# isg_AL11b_equip_chip_board_passive.net
KiCad netlist of a schematic drawn in Altium Designer
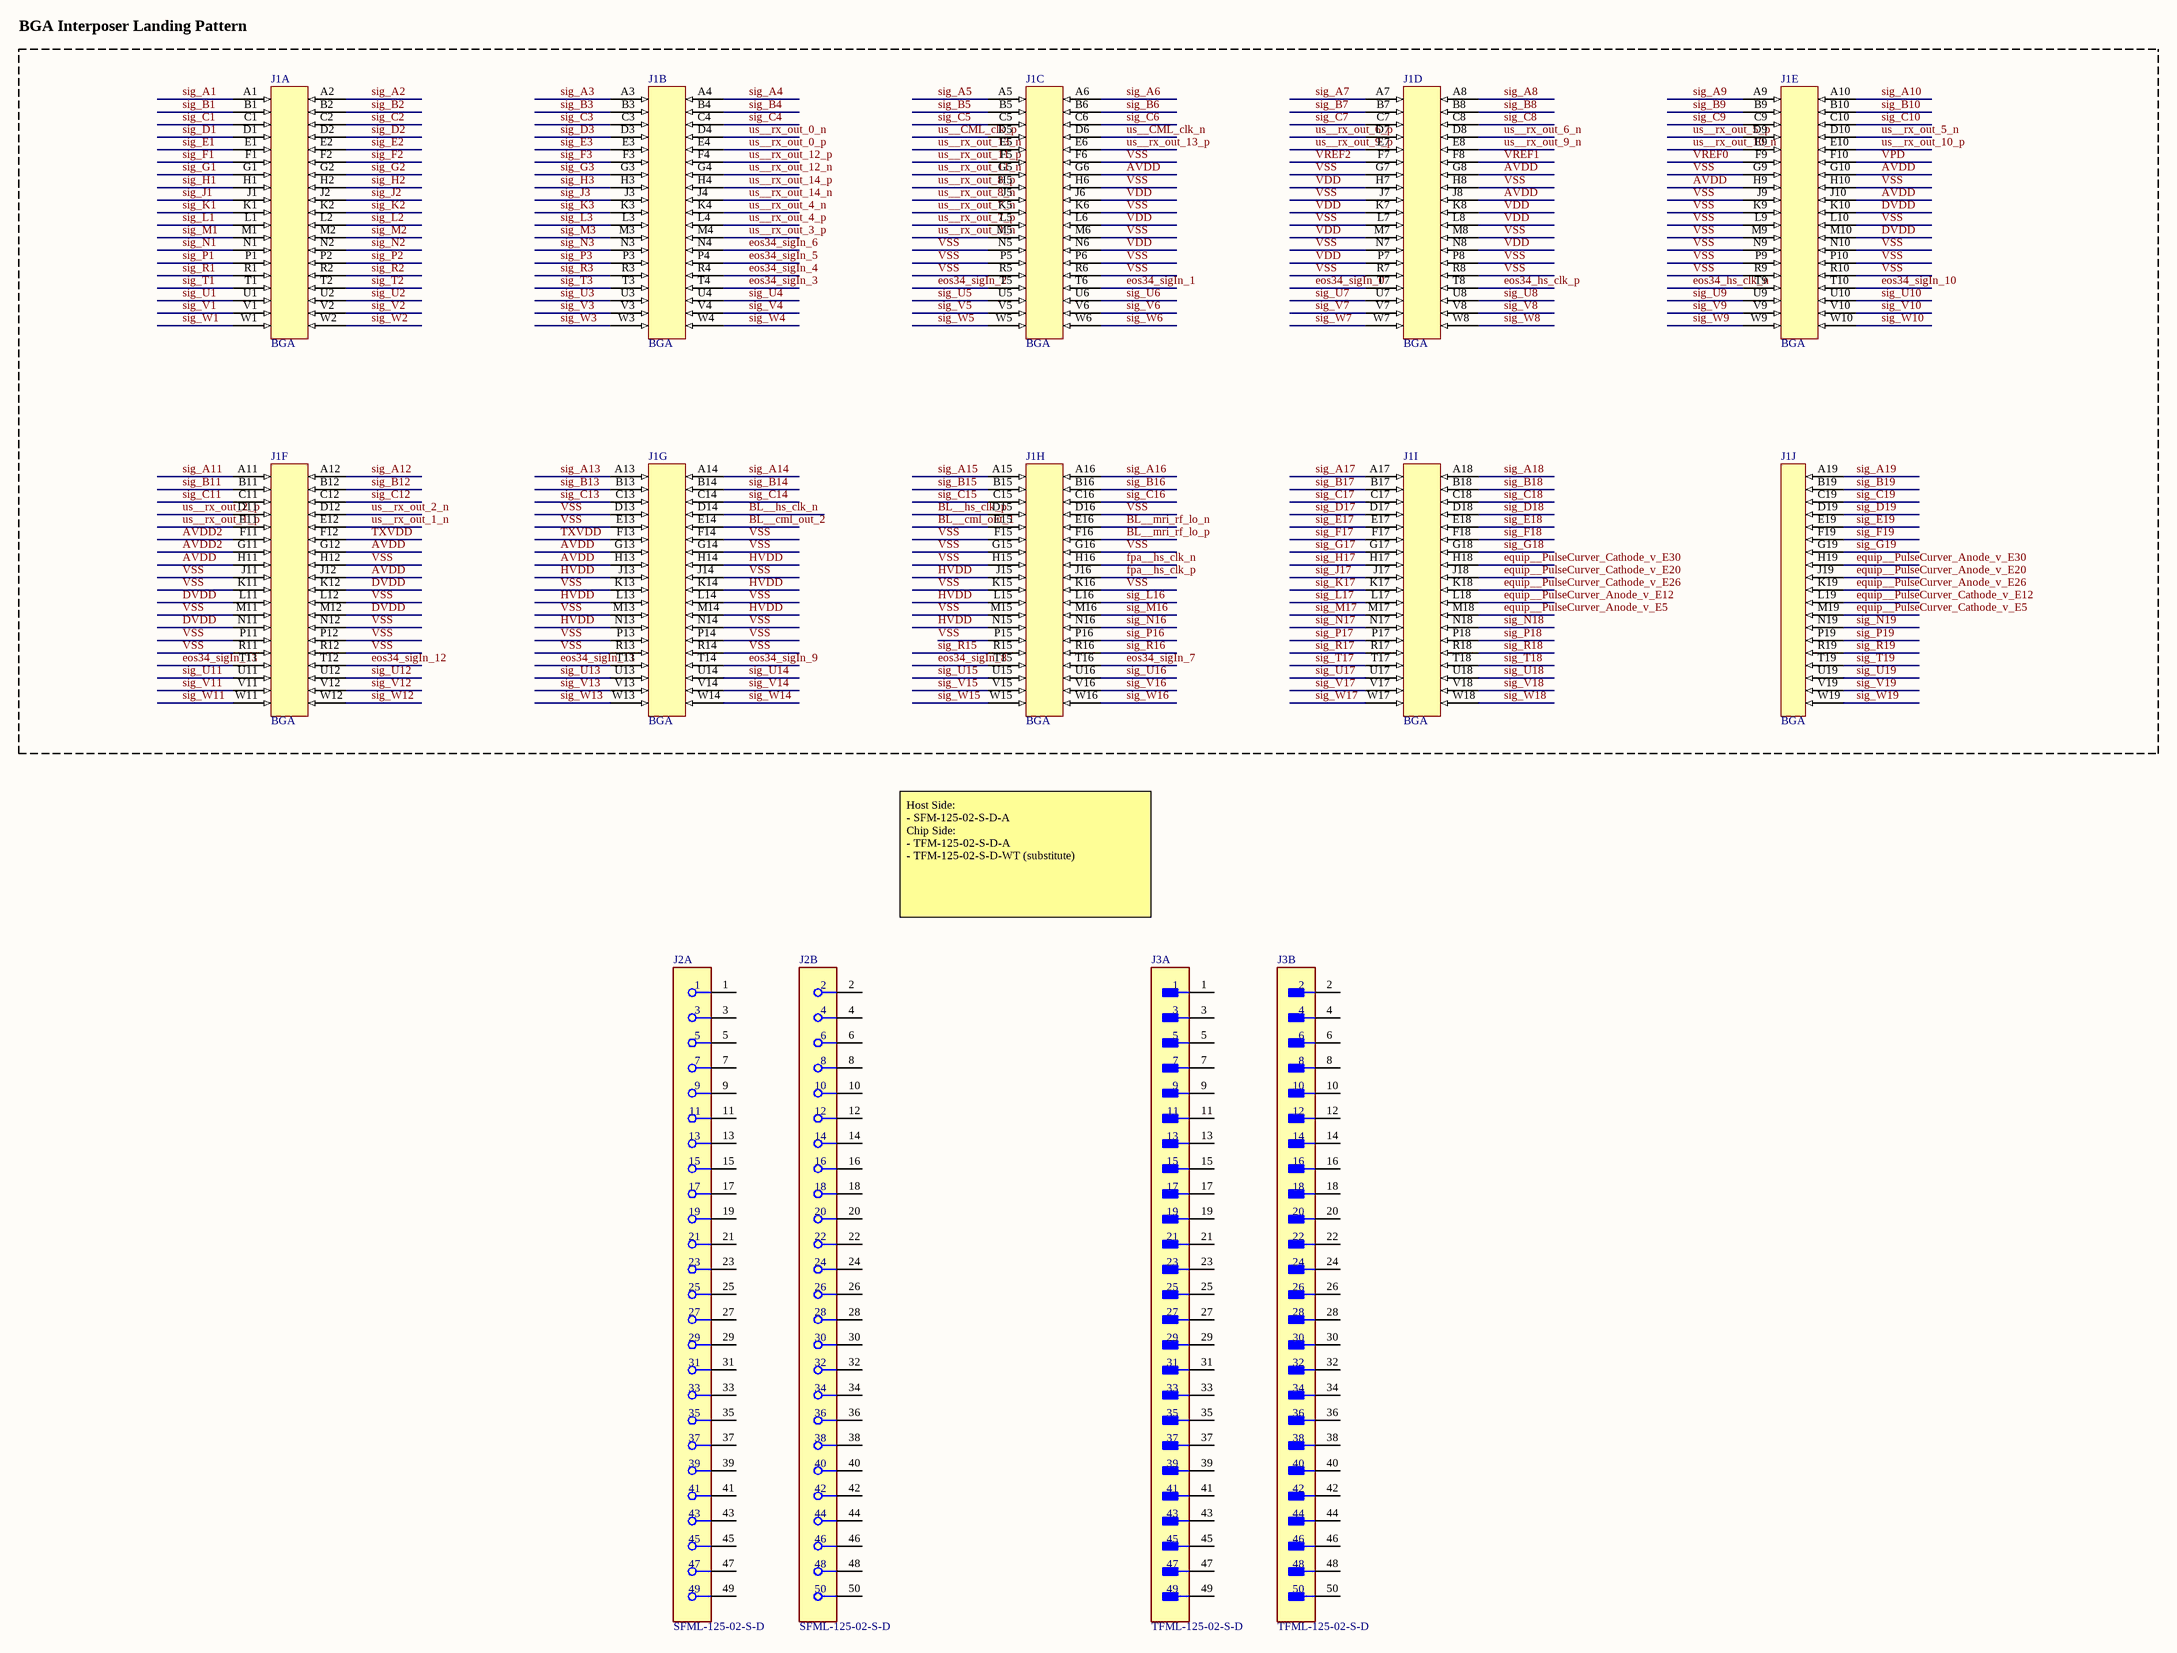
[diagram p0: isg_AL11b_equip_chip_board_passive.SchDoc]

(export (version "E")
  (design (tool "Eeschema 10.0.6"))
  (components
    (comp (ref "J1")
      (value "BGA")
      (footprint "BGA361x19_CHIP_BOARD_TOP")
      (libsource (lib "AL11b") (part "BGA"))
    )
    (comp (ref "J2")
      (value "SFML-125-02-S-D")
      (footprint "FP-SFML-125-02-S-D-MFG")
      (description "CONN RCPT 50POS 0.05 GOLD SMD")
      (libsource (lib "Altium Content Vault") (part "81018408ad8334d3fec81fb021a27ac"))
    )
    (comp (ref "J3")
      (value "TFML-125-02-S-D")
      (footprint "FP-TFML-125-02-S-D-MFG")
      (description "CONN HEADER SMD 50POS 1.27MM")
      (libsource (lib "Altium Content Vault") (part "0c4f4a43de66d56b98fa02f2c160411"))
    )
  )
  (nets
    (net (code "1") (name "/AVDD") (class "Default")
      (node (ref "J1") (pin "G10") (pintype "input"))
      (node (ref "J1") (pin "G12") (pintype "input"))
      (node (ref "J1") (pin "G13") (pintype "input"))
      (node (ref "J1") (pin "G6") (pintype "input"))
      (node (ref "J1") (pin "G8") (pintype "input"))
      (node (ref "J1") (pin "H11") (pintype "input"))
      (node (ref "J1") (pin "H13") (pintype "input"))
      (node (ref "J1") (pin "H9") (pintype "input"))
      (node (ref "J1") (pin "J10") (pintype "input"))
      (node (ref "J1") (pin "J12") (pintype "input"))
      (node (ref "J1") (pin "J8") (pintype "input"))
    )
    (net (code "2") (name "/AVDD2") (class "Default")
      (node (ref "J1") (pin "F11") (pintype "input"))
      (node (ref "J1") (pin "G11") (pintype "input"))
    )
    (net (code "3") (name "/BL__cml_out_1") (class "Default") (node (ref "J1") (pin "E15") (pintype "input")))
    (net (code "4") (name "/BL__cml_out_2") (class "Default") (node (ref "J1") (pin "E14") (pintype "input")))
    (net (code "5") (name "/BL__hs_clk_n") (class "Default") (node (ref "J1") (pin "D14") (pintype "input")))
    (net (code "6") (name "/BL__hs_clk_p") (class "Default") (node (ref "J1") (pin "D15") (pintype "input")))
    (net (code "7") (name "/BL__mri_rf_lo_n") (class "Default")
      (node (ref "J1") (pin "E16") (pintype "input"))
    )
    (net (code "8") (name "/BL__mri_rf_lo_p") (class "Default")
      (node (ref "J1") (pin "F16") (pintype "input"))
    )
    (net (code "9") (name "/DVDD") (class "Default")
      (node (ref "J1") (pin "K10") (pintype "input"))
      (node (ref "J1") (pin "K12") (pintype "input"))
      (node (ref "J1") (pin "L11") (pintype "input"))
      (node (ref "J1") (pin "M10") (pintype "input"))
      (node (ref "J1") (pin "M12") (pintype "input"))
      (node (ref "J1") (pin "N11") (pintype "input"))
    )
    (net (code "10") (name "/HVDD") (class "Default")
      (node (ref "J1") (pin "H14") (pintype "input"))
      (node (ref "J1") (pin "J13") (pintype "input"))
      (node (ref "J1") (pin "J15") (pintype "input"))
      (node (ref "J1") (pin "K14") (pintype "input"))
      (node (ref "J1") (pin "L13") (pintype "input"))
      (node (ref "J1") (pin "L15") (pintype "input"))
      (node (ref "J1") (pin "M14") (pintype "input"))
      (node (ref "J1") (pin "N13") (pintype "input"))
      (node (ref "J1") (pin "N15") (pintype "input"))
    )
    (net (code "11") (name "/TXVDD") (class "Default")
      (node (ref "J1") (pin "F12") (pintype "input"))
      (node (ref "J1") (pin "F13") (pintype "input"))
    )
    (net (code "12") (name "/VDD") (class "Default")
      (node (ref "J1") (pin "H7") (pintype "input"))
      (node (ref "J1") (pin "J6") (pintype "input"))
      (node (ref "J1") (pin "K7") (pintype "input"))
      (node (ref "J1") (pin "K8") (pintype "input"))
      (node (ref "J1") (pin "L6") (pintype "input"))
      (node (ref "J1") (pin "L8") (pintype "input"))
      (node (ref "J1") (pin "M7") (pintype "input"))
      (node (ref "J1") (pin "N6") (pintype "input"))
      (node (ref "J1") (pin "N8") (pintype "input"))
      (node (ref "J1") (pin "P7") (pintype "input"))
    )
    (net (code "13") (name "/VPD") (class "Default") (node (ref "J1") (pin "F10") (pintype "input")))
    (net (code "14") (name "/VREF0") (class "Default") (node (ref "J1") (pin "F9") (pintype "input")))
    (net (code "15") (name "/VREF1") (class "Default") (node (ref "J1") (pin "F8") (pintype "input")))
    (net (code "16") (name "/VREF2") (class "Default") (node (ref "J1") (pin "F7") (pintype "input")))
    (net (code "17") (name "/VSS") (class "Default")
      (node (ref "J1") (pin "D13") (pintype "input"))
      (node (ref "J1") (pin "D16") (pintype "input"))
      (node (ref "J1") (pin "E13") (pintype "input"))
      (node (ref "J1") (pin "F14") (pintype "input"))
      (node (ref "J1") (pin "F15") (pintype "input"))
      (node (ref "J1") (pin "F6") (pintype "input"))
      (node (ref "J1") (pin "G14") (pintype "input"))
      (node (ref "J1") (pin "G15") (pintype "input"))
      (node (ref "J1") (pin "G16") (pintype "input"))
      (node (ref "J1") (pin "G7") (pintype "input"))
      (node (ref "J1") (pin "G9") (pintype "input"))
      (node (ref "J1") (pin "H10") (pintype "input"))
      (node (ref "J1") (pin "H12") (pintype "input"))
      (node (ref "J1") (pin "H15") (pintype "input"))
      (node (ref "J1") (pin "H6") (pintype "input"))
      (node (ref "J1") (pin "H8") (pintype "input"))
      (node (ref "J1") (pin "J11") (pintype "input"))
      (node (ref "J1") (pin "J14") (pintype "input"))
      (node (ref "J1") (pin "J7") (pintype "input"))
      (node (ref "J1") (pin "J9") (pintype "input"))
      (node (ref "J1") (pin "K11") (pintype "input"))
      (node (ref "J1") (pin "K13") (pintype "input"))
      (node (ref "J1") (pin "K15") (pintype "input"))
      (node (ref "J1") (pin "K16") (pintype "input"))
      (node (ref "J1") (pin "K6") (pintype "input"))
      (node (ref "J1") (pin "K9") (pintype "input"))
      (node (ref "J1") (pin "L10") (pintype "input"))
      (node (ref "J1") (pin "L12") (pintype "input"))
      (node (ref "J1") (pin "L14") (pintype "input"))
      (node (ref "J1") (pin "L7") (pintype "input"))
      (node (ref "J1") (pin "L9") (pintype "input"))
      (node (ref "J1") (pin "M11") (pintype "input"))
      (node (ref "J1") (pin "M13") (pintype "input"))
      (node (ref "J1") (pin "M15") (pintype "input"))
      (node (ref "J1") (pin "M6") (pintype "input"))
      (node (ref "J1") (pin "M8") (pintype "input"))
      (node (ref "J1") (pin "M9") (pintype "input"))
      (node (ref "J1") (pin "N10") (pintype "input"))
      (node (ref "J1") (pin "N12") (pintype "input"))
      (node (ref "J1") (pin "N14") (pintype "input"))
      (node (ref "J1") (pin "N5") (pintype "input"))
      (node (ref "J1") (pin "N7") (pintype "input"))
      (node (ref "J1") (pin "N9") (pintype "input"))
      (node (ref "J1") (pin "P10") (pintype "input"))
      (node (ref "J1") (pin "P11") (pintype "input"))
      (node (ref "J1") (pin "P12") (pintype "input"))
      (node (ref "J1") (pin "P13") (pintype "input"))
      (node (ref "J1") (pin "P14") (pintype "input"))
      (node (ref "J1") (pin "P15") (pintype "input"))
      (node (ref "J1") (pin "P5") (pintype "input"))
      (node (ref "J1") (pin "P6") (pintype "input"))
      (node (ref "J1") (pin "P8") (pintype "input"))
      (node (ref "J1") (pin "P9") (pintype "input"))
      (node (ref "J1") (pin "R10") (pintype "input"))
      (node (ref "J1") (pin "R11") (pintype "input"))
      (node (ref "J1") (pin "R12") (pintype "input"))
      (node (ref "J1") (pin "R13") (pintype "input"))
      (node (ref "J1") (pin "R14") (pintype "input"))
      (node (ref "J1") (pin "R5") (pintype "input"))
      (node (ref "J1") (pin "R6") (pintype "input"))
      (node (ref "J1") (pin "R7") (pintype "input"))
      (node (ref "J1") (pin "R8") (pintype "input"))
      (node (ref "J1") (pin "R9") (pintype "input"))
    )
    (net (code "18") (name "/eos34_hs_clk_n") (class "Default")
      (node (ref "J1") (pin "T9") (pintype "input"))
    )
    (net (code "19") (name "/eos34_hs_clk_p") (class "Default")
      (node (ref "J1") (pin "T8") (pintype "input"))
    )
    (net (code "20") (name "/eos34_sigIn_0") (class "Default") (node (ref "J1") (pin "T7") (pintype "input")))
    (net (code "21") (name "/eos34_sigIn_1") (class "Default") (node (ref "J1") (pin "T6") (pintype "input")))
    (net (code "22") (name "/eos34_sigIn_2") (class "Default") (node (ref "J1") (pin "T5") (pintype "input")))
    (net (code "23") (name "/eos34_sigIn_3") (class "Default") (node (ref "J1") (pin "T4") (pintype "input")))
    (net (code "24") (name "/eos34_sigIn_4") (class "Default") (node (ref "J1") (pin "R4") (pintype "input")))
    (net (code "25") (name "/eos34_sigIn_5") (class "Default") (node (ref "J1") (pin "P4") (pintype "input")))
    (net (code "26") (name "/eos34_sigIn_6") (class "Default") (node (ref "J1") (pin "N4") (pintype "input")))
    (net (code "27") (name "/eos34_sigIn_7") (class "Default")
      (node (ref "J1") (pin "T16") (pintype "input"))
    )
    (net (code "28") (name "/eos34_sigIn_8") (class "Default")
      (node (ref "J1") (pin "T15") (pintype "input"))
    )
    (net (code "29") (name "/eos34_sigIn_9") (class "Default")
      (node (ref "J1") (pin "T14") (pintype "input"))
    )
    (net (code "30") (name "/eos34_sigIn_10") (class "Default")
      (node (ref "J1") (pin "T10") (pintype "input"))
    )
    (net (code "31") (name "/eos34_sigIn_11") (class "Default")
      (node (ref "J1") (pin "T13") (pintype "input"))
    )
    (net (code "32") (name "/eos34_sigIn_12") (class "Default")
      (node (ref "J1") (pin "T12") (pintype "input"))
    )
    (net (code "33") (name "/eos34_sigIn_13") (class "Default")
      (node (ref "J1") (pin "T11") (pintype "input"))
    )
    (net (code "34") (name "/equip__PulseCurver_Anode_v_E5") (class "Default")
      (node (ref "J1") (pin "M18") (pintype "input"))
    )
    (net (code "35") (name "/equip__PulseCurver_Anode_v_E12") (class "Default")
      (node (ref "J1") (pin "L18") (pintype "input"))
    )
    (net (code "36") (name "/equip__PulseCurver_Anode_v_E20") (class "Default")
      (node (ref "J1") (pin "J19") (pintype "input"))
    )
    (net (code "37") (name "/equip__PulseCurver_Anode_v_E26") (class "Default")
      (node (ref "J1") (pin "K19") (pintype "input"))
    )
    (net (code "38") (name "/equip__PulseCurver_Anode_v_E30") (class "Default")
      (node (ref "J1") (pin "H19") (pintype "input"))
    )
    (net (code "39") (name "/equip__PulseCurver_Cathode_v_E5") (class "Default")
      (node (ref "J1") (pin "M19") (pintype "input"))
    )
    (net (code "40") (name "/equip__PulseCurver_Cathode_v_E12") (class "Default")
      (node (ref "J1") (pin "L19") (pintype "input"))
    )
    (net (code "41") (name "/equip__PulseCurver_Cathode_v_E20") (class "Default")
      (node (ref "J1") (pin "J18") (pintype "input"))
    )
    (net (code "42") (name "/equip__PulseCurver_Cathode_v_E26") (class "Default")
      (node (ref "J1") (pin "K18") (pintype "input"))
    )
    (net (code "43") (name "/equip__PulseCurver_Cathode_v_E30") (class "Default")
      (node (ref "J1") (pin "H18") (pintype "input"))
    )
    (net (code "44") (name "/fpa__hs_clk_n") (class "Default")
      (node (ref "J1") (pin "H16") (pintype "input"))
    )
    (net (code "45") (name "/fpa__hs_clk_p") (class "Default")
      (node (ref "J1") (pin "J16") (pintype "input"))
    )
    (net (code "46") (name "/sig_A1") (class "Default") (node (ref "J1") (pin "A1") (pintype "input")))
    (net (code "47") (name "/sig_A2") (class "Default") (node (ref "J1") (pin "A2") (pintype "input")))
    (net (code "48") (name "/sig_A3") (class "Default") (node (ref "J1") (pin "A3") (pintype "input")))
    (net (code "49") (name "/sig_A4") (class "Default") (node (ref "J1") (pin "A4") (pintype "input")))
    (net (code "50") (name "/sig_A5") (class "Default") (node (ref "J1") (pin "A5") (pintype "input")))
    (net (code "51") (name "/sig_A6") (class "Default") (node (ref "J1") (pin "A6") (pintype "input")))
    (net (code "52") (name "/sig_A7") (class "Default") (node (ref "J1") (pin "A7") (pintype "input")))
    (net (code "53") (name "/sig_A8") (class "Default") (node (ref "J1") (pin "A8") (pintype "input")))
    (net (code "54") (name "/sig_A9") (class "Default") (node (ref "J1") (pin "A9") (pintype "input")))
    (net (code "55") (name "/sig_A10") (class "Default") (node (ref "J1") (pin "A10") (pintype "input")))
    (net (code "56") (name "/sig_A11") (class "Default") (node (ref "J1") (pin "A11") (pintype "input")))
    (net (code "57") (name "/sig_A12") (class "Default") (node (ref "J1") (pin "A12") (pintype "input")))
    (net (code "58") (name "/sig_A13") (class "Default") (node (ref "J1") (pin "A13") (pintype "input")))
    (net (code "59") (name "/sig_A14") (class "Default") (node (ref "J1") (pin "A14") (pintype "input")))
    (net (code "60") (name "/sig_A15") (class "Default") (node (ref "J1") (pin "A15") (pintype "input")))
    (net (code "61") (name "/sig_A16") (class "Default") (node (ref "J1") (pin "A16") (pintype "input")))
    (net (code "62") (name "/sig_A17") (class "Default") (node (ref "J1") (pin "A17") (pintype "input")))
    (net (code "63") (name "/sig_A18") (class "Default") (node (ref "J1") (pin "A18") (pintype "input")))
    (net (code "64") (name "/sig_A19") (class "Default") (node (ref "J1") (pin "A19") (pintype "input")))
    (net (code "65") (name "/sig_B1") (class "Default") (node (ref "J1") (pin "B1") (pintype "input")))
    (net (code "66") (name "/sig_B2") (class "Default") (node (ref "J1") (pin "B2") (pintype "input")))
    (net (code "67") (name "/sig_B3") (class "Default") (node (ref "J1") (pin "B3") (pintype "input")))
    (net (code "68") (name "/sig_B4") (class "Default") (node (ref "J1") (pin "B4") (pintype "input")))
    (net (code "69") (name "/sig_B5") (class "Default") (node (ref "J1") (pin "B5") (pintype "input")))
    (net (code "70") (name "/sig_B6") (class "Default") (node (ref "J1") (pin "B6") (pintype "input")))
    (net (code "71") (name "/sig_B7") (class "Default") (node (ref "J1") (pin "B7") (pintype "input")))
    (net (code "72") (name "/sig_B8") (class "Default") (node (ref "J1") (pin "B8") (pintype "input")))
    (net (code "73") (name "/sig_B9") (class "Default") (node (ref "J1") (pin "B9") (pintype "input")))
    (net (code "74") (name "/sig_B10") (class "Default") (node (ref "J1") (pin "B10") (pintype "input")))
    (net (code "75") (name "/sig_B11") (class "Default") (node (ref "J1") (pin "B11") (pintype "input")))
    (net (code "76") (name "/sig_B12") (class "Default") (node (ref "J1") (pin "B12") (pintype "input")))
    (net (code "77") (name "/sig_B13") (class "Default") (node (ref "J1") (pin "B13") (pintype "input")))
    (net (code "78") (name "/sig_B14") (class "Default") (node (ref "J1") (pin "B14") (pintype "input")))
    (net (code "79") (name "/sig_B15") (class "Default") (node (ref "J1") (pin "B15") (pintype "input")))
    (net (code "80") (name "/sig_B16") (class "Default") (node (ref "J1") (pin "B16") (pintype "input")))
    (net (code "81") (name "/sig_B17") (class "Default") (node (ref "J1") (pin "B17") (pintype "input")))
    (net (code "82") (name "/sig_B18") (class "Default") (node (ref "J1") (pin "B18") (pintype "input")))
    (net (code "83") (name "/sig_B19") (class "Default") (node (ref "J1") (pin "B19") (pintype "input")))
    (net (code "84") (name "/sig_C1") (class "Default") (node (ref "J1") (pin "C1") (pintype "input")))
    (net (code "85") (name "/sig_C2") (class "Default") (node (ref "J1") (pin "C2") (pintype "input")))
    (net (code "86") (name "/sig_C3") (class "Default") (node (ref "J1") (pin "C3") (pintype "input")))
    (net (code "87") (name "/sig_C4") (class "Default") (node (ref "J1") (pin "C4") (pintype "input")))
    (net (code "88") (name "/sig_C5") (class "Default") (node (ref "J1") (pin "C5") (pintype "input")))
    (net (code "89") (name "/sig_C6") (class "Default") (node (ref "J1") (pin "C6") (pintype "input")))
    (net (code "90") (name "/sig_C7") (class "Default") (node (ref "J1") (pin "C7") (pintype "input")))
    (net (code "91") (name "/sig_C8") (class "Default") (node (ref "J1") (pin "C8") (pintype "input")))
    (net (code "92") (name "/sig_C9") (class "Default") (node (ref "J1") (pin "C9") (pintype "input")))
    (net (code "93") (name "/sig_C10") (class "Default") (node (ref "J1") (pin "C10") (pintype "input")))
    (net (code "94") (name "/sig_C11") (class "Default") (node (ref "J1") (pin "C11") (pintype "input")))
    (net (code "95") (name "/sig_C12") (class "Default") (node (ref "J1") (pin "C12") (pintype "input")))
    (net (code "96") (name "/sig_C13") (class "Default") (node (ref "J1") (pin "C13") (pintype "input")))
    (net (code "97") (name "/sig_C14") (class "Default") (node (ref "J1") (pin "C14") (pintype "input")))
    (net (code "98") (name "/sig_C15") (class "Default") (node (ref "J1") (pin "C15") (pintype "input")))
    (net (code "99") (name "/sig_C16") (class "Default") (node (ref "J1") (pin "C16") (pintype "input")))
    (net (code "100") (name "/sig_C17") (class "Default") (node (ref "J1") (pin "C17") (pintype "input")))
    (net (code "101") (name "/sig_C18") (class "Default") (node (ref "J1") (pin "C18") (pintype "input")))
    (net (code "102") (name "/sig_C19") (class "Default") (node (ref "J1") (pin "C19") (pintype "input")))
    (net (code "103") (name "/sig_D1") (class "Default") (node (ref "J1") (pin "D1") (pintype "input")))
    (net (code "104") (name "/sig_D2") (class "Default") (node (ref "J1") (pin "D2") (pintype "input")))
    (net (code "105") (name "/sig_D3") (class "Default") (node (ref "J1") (pin "D3") (pintype "input")))
    (net (code "106") (name "/sig_D17") (class "Default") (node (ref "J1") (pin "D17") (pintype "input")))
    (net (code "107") (name "/sig_D18") (class "Default") (node (ref "J1") (pin "D18") (pintype "input")))
    (net (code "108") (name "/sig_D19") (class "Default") (node (ref "J1") (pin "D19") (pintype "input")))
    (net (code "109") (name "/sig_E1") (class "Default") (node (ref "J1") (pin "E1") (pintype "input")))
    (net (code "110") (name "/sig_E2") (class "Default") (node (ref "J1") (pin "E2") (pintype "input")))
    (net (code "111") (name "/sig_E3") (class "Default") (node (ref "J1") (pin "E3") (pintype "input")))
    (net (code "112") (name "/sig_E17") (class "Default") (node (ref "J1") (pin "E17") (pintype "input")))
    (net (code "113") (name "/sig_E18") (class "Default") (node (ref "J1") (pin "E18") (pintype "input")))
    (net (code "114") (name "/sig_E19") (class "Default") (node (ref "J1") (pin "E19") (pintype "input")))
    (net (code "115") (name "/sig_F1") (class "Default") (node (ref "J1") (pin "F1") (pintype "input")))
    (net (code "116") (name "/sig_F2") (class "Default") (node (ref "J1") (pin "F2") (pintype "input")))
    (net (code "117") (name "/sig_F3") (class "Default") (node (ref "J1") (pin "F3") (pintype "input")))
    (net (code "118") (name "/sig_F17") (class "Default") (node (ref "J1") (pin "F17") (pintype "input")))
    (net (code "119") (name "/sig_F18") (class "Default") (node (ref "J1") (pin "F18") (pintype "input")))
    (net (code "120") (name "/sig_F19") (class "Default") (node (ref "J1") (pin "F19") (pintype "input")))
    (net (code "121") (name "/sig_G1") (class "Default") (node (ref "J1") (pin "G1") (pintype "input")))
    (net (code "122") (name "/sig_G2") (class "Default") (node (ref "J1") (pin "G2") (pintype "input")))
    (net (code "123") (name "/sig_G3") (class "Default") (node (ref "J1") (pin "G3") (pintype "input")))
    (net (code "124") (name "/sig_G17") (class "Default") (node (ref "J1") (pin "G17") (pintype "input")))
    (net (code "125") (name "/sig_G18") (class "Default") (node (ref "J1") (pin "G18") (pintype "input")))
    (net (code "126") (name "/sig_G19") (class "Default") (node (ref "J1") (pin "G19") (pintype "input")))
    (net (code "127") (name "/sig_H1") (class "Default") (node (ref "J1") (pin "H1") (pintype "input")))
    (net (code "128") (name "/sig_H2") (class "Default") (node (ref "J1") (pin "H2") (pintype "input")))
    (net (code "129") (name "/sig_H3") (class "Default") (node (ref "J1") (pin "H3") (pintype "input")))
    (net (code "130") (name "/sig_H17") (class "Default") (node (ref "J1") (pin "H17") (pintype "input")))
    (net (code "131") (name "/sig_J1") (class "Default") (node (ref "J1") (pin "J1") (pintype "input")))
    (net (code "132") (name "/sig_J2") (class "Default") (node (ref "J1") (pin "J2") (pintype "input")))
    (net (code "133") (name "/sig_J3") (class "Default") (node (ref "J1") (pin "J3") (pintype "input")))
    (net (code "134") (name "/sig_J17") (class "Default") (node (ref "J1") (pin "J17") (pintype "input")))
    (net (code "135") (name "/sig_K1") (class "Default") (node (ref "J1") (pin "K1") (pintype "input")))
    (net (code "136") (name "/sig_K2") (class "Default") (node (ref "J1") (pin "K2") (pintype "input")))
    (net (code "137") (name "/sig_K3") (class "Default") (node (ref "J1") (pin "K3") (pintype "input")))
    (net (code "138") (name "/sig_K17") (class "Default") (node (ref "J1") (pin "K17") (pintype "input")))
    (net (code "139") (name "/sig_L1") (class "Default") (node (ref "J1") (pin "L1") (pintype "input")))
    (net (code "140") (name "/sig_L2") (class "Default") (node (ref "J1") (pin "L2") (pintype "input")))
    (net (code "141") (name "/sig_L3") (class "Default") (node (ref "J1") (pin "L3") (pintype "input")))
    (net (code "142") (name "/sig_L16") (class "Default") (node (ref "J1") (pin "L16") (pintype "input")))
    (net (code "143") (name "/sig_L17") (class "Default") (node (ref "J1") (pin "L17") (pintype "input")))
    (net (code "144") (name "/sig_M1") (class "Default") (node (ref "J1") (pin "M1") (pintype "input")))
    (net (code "145") (name "/sig_M2") (class "Default") (node (ref "J1") (pin "M2") (pintype "input")))
    (net (code "146") (name "/sig_M3") (class "Default") (node (ref "J1") (pin "M3") (pintype "input")))
    (net (code "147") (name "/sig_M16") (class "Default") (node (ref "J1") (pin "M16") (pintype "input")))
    (net (code "148") (name "/sig_M17") (class "Default") (node (ref "J1") (pin "M17") (pintype "input")))
    (net (code "149") (name "/sig_N1") (class "Default") (node (ref "J1") (pin "N1") (pintype "input")))
    (net (code "150") (name "/sig_N2") (class "Default") (node (ref "J1") (pin "N2") (pintype "input")))
    (net (code "151") (name "/sig_N3") (class "Default") (node (ref "J1") (pin "N3") (pintype "input")))
    (net (code "152") (name "/sig_N16") (class "Default") (node (ref "J1") (pin "N16") (pintype "input")))
    (net (code "153") (name "/sig_N17") (class "Default") (node (ref "J1") (pin "N17") (pintype "input")))
    (net (code "154") (name "/sig_N18") (class "Default") (node (ref "J1") (pin "N18") (pintype "input")))
    (net (code "155") (name "/sig_N19") (class "Default") (node (ref "J1") (pin "N19") (pintype "input")))
    (net (code "156") (name "/sig_P1") (class "Default") (node (ref "J1") (pin "P1") (pintype "input")))
    (net (code "157") (name "/sig_P2") (class "Default") (node (ref "J1") (pin "P2") (pintype "input")))
    (net (code "158") (name "/sig_P3") (class "Default") (node (ref "J1") (pin "P3") (pintype "input")))
    (net (code "159") (name "/sig_P16") (class "Default") (node (ref "J1") (pin "P16") (pintype "input")))
    (net (code "160") (name "/sig_P17") (class "Default") (node (ref "J1") (pin "P17") (pintype "input")))
    (net (code "161") (name "/sig_P18") (class "Default") (node (ref "J1") (pin "P18") (pintype "input")))
    (net (code "162") (name "/sig_P19") (class "Default") (node (ref "J1") (pin "P19") (pintype "input")))
    (net (code "163") (name "/sig_R1") (class "Default") (node (ref "J1") (pin "R1") (pintype "input")))
    (net (code "164") (name "/sig_R2") (class "Default") (node (ref "J1") (pin "R2") (pintype "input")))
    (net (code "165") (name "/sig_R3") (class "Default") (node (ref "J1") (pin "R3") (pintype "input")))
    (net (code "166") (name "/sig_R15") (class "Default") (node (ref "J1") (pin "R15") (pintype "input")))
    (net (code "167") (name "/sig_R16") (class "Default") (node (ref "J1") (pin "R16") (pintype "input")))
    (net (code "168") (name "/sig_R17") (class "Default") (node (ref "J1") (pin "R17") (pintype "input")))
    (net (code "169") (name "/sig_R18") (class "Default") (node (ref "J1") (pin "R18") (pintype "input")))
    (net (code "170") (name "/sig_R19") (class "Default") (node (ref "J1") (pin "R19") (pintype "input")))
    (net (code "171") (name "/sig_T1") (class "Default") (node (ref "J1") (pin "T1") (pintype "input")))
    (net (code "172") (name "/sig_T2") (class "Default") (node (ref "J1") (pin "T2") (pintype "input")))
    (net (code "173") (name "/sig_T3") (class "Default") (node (ref "J1") (pin "T3") (pintype "input")))
    (net (code "174") (name "/sig_T17") (class "Default") (node (ref "J1") (pin "T17") (pintype "input")))
    (net (code "175") (name "/sig_T18") (class "Default") (node (ref "J1") (pin "T18") (pintype "input")))
    (net (code "176") (name "/sig_T19") (class "Default") (node (ref "J1") (pin "T19") (pintype "input")))
    (net (code "177") (name "/sig_U1") (class "Default") (node (ref "J1") (pin "U1") (pintype "input")))
    (net (code "178") (name "/sig_U2") (class "Default") (node (ref "J1") (pin "U2") (pintype "input")))
    (net (code "179") (name "/sig_U3") (class "Default") (node (ref "J1") (pin "U3") (pintype "input")))
    (net (code "180") (name "/sig_U4") (class "Default") (node (ref "J1") (pin "U4") (pintype "input")))
    (net (code "181") (name "/sig_U5") (class "Default") (node (ref "J1") (pin "U5") (pintype "input")))
    (net (code "182") (name "/sig_U6") (class "Default") (node (ref "J1") (pin "U6") (pintype "input")))
    (net (code "183") (name "/sig_U7") (class "Default") (node (ref "J1") (pin "U7") (pintype "input")))
    (net (code "184") (name "/sig_U8") (class "Default") (node (ref "J1") (pin "U8") (pintype "input")))
    (net (code "185") (name "/sig_U9") (class "Default") (node (ref "J1") (pin "U9") (pintype "input")))
    (net (code "186") (name "/sig_U10") (class "Default") (node (ref "J1") (pin "U10") (pintype "input")))
    (net (code "187") (name "/sig_U11") (class "Default") (node (ref "J1") (pin "U11") (pintype "input")))
    (net (code "188") (name "/sig_U12") (class "Default") (node (ref "J1") (pin "U12") (pintype "input")))
    (net (code "189") (name "/sig_U13") (class "Default") (node (ref "J1") (pin "U13") (pintype "input")))
    (net (code "190") (name "/sig_U14") (class "Default") (node (ref "J1") (pin "U14") (pintype "input")))
    (net (code "191") (name "/sig_U15") (class "Default") (node (ref "J1") (pin "U15") (pintype "input")))
    (net (code "192") (name "/sig_U16") (class "Default") (node (ref "J1") (pin "U16") (pintype "input")))
    (net (code "193") (name "/sig_U17") (class "Default") (node (ref "J1") (pin "U17") (pintype "input")))
    (net (code "194") (name "/sig_U18") (class "Default") (node (ref "J1") (pin "U18") (pintype "input")))
    (net (code "195") (name "/sig_U19") (class "Default") (node (ref "J1") (pin "U19") (pintype "input")))
    (net (code "196") (name "/sig_V1") (class "Default") (node (ref "J1") (pin "V1") (pintype "input")))
    (net (code "197") (name "/sig_V2") (class "Default") (node (ref "J1") (pin "V2") (pintype "input")))
    (net (code "198") (name "/sig_V3") (class "Default") (node (ref "J1") (pin "V3") (pintype "input")))
    (net (code "199") (name "/sig_V4") (class "Default") (node (ref "J1") (pin "V4") (pintype "input")))
    (net (code "200") (name "/sig_V5") (class "Default") (node (ref "J1") (pin "V5") (pintype "input")))
    (net (code "201") (name "/sig_V6") (class "Default") (node (ref "J1") (pin "V6") (pintype "input")))
    (net (code "202") (name "/sig_V7") (class "Default") (node (ref "J1") (pin "V7") (pintype "input")))
    (net (code "203") (name "/sig_V8") (class "Default") (node (ref "J1") (pin "V8") (pintype "input")))
    (net (code "204") (name "/sig_V9") (class "Default") (node (ref "J1") (pin "V9") (pintype "input")))
    (net (code "205") (name "/sig_V10") (class "Default") (node (ref "J1") (pin "V10") (pintype "input")))
    (net (code "206") (name "/sig_V11") (class "Default") (node (ref "J1") (pin "V11") (pintype "input")))
    (net (code "207") (name "/sig_V12") (class "Default") (node (ref "J1") (pin "V12") (pintype "input")))
    (net (code "208") (name "/sig_V13") (class "Default") (node (ref "J1") (pin "V13") (pintype "input")))
    (net (code "209") (name "/sig_V14") (class "Default") (node (ref "J1") (pin "V14") (pintype "input")))
    (net (code "210") (name "/sig_V15") (class "Default") (node (ref "J1") (pin "V15") (pintype "input")))
    (net (code "211") (name "/sig_V16") (class "Default") (node (ref "J1") (pin "V16") (pintype "input")))
    (net (code "212") (name "/sig_V17") (class "Default") (node (ref "J1") (pin "V17") (pintype "input")))
    (net (code "213") (name "/sig_V18") (class "Default") (node (ref "J1") (pin "V18") (pintype "input")))
    (net (code "214") (name "/sig_V19") (class "Default") (node (ref "J1") (pin "V19") (pintype "input")))
    (net (code "215") (name "/sig_W1") (class "Default") (node (ref "J1") (pin "W1") (pintype "input")))
    (net (code "216") (name "/sig_W2") (class "Default") (node (ref "J1") (pin "W2") (pintype "input")))
    (net (code "217") (name "/sig_W3") (class "Default") (node (ref "J1") (pin "W3") (pintype "input")))
    (net (code "218") (name "/sig_W4") (class "Default") (node (ref "J1") (pin "W4") (pintype "input")))
    (net (code "219") (name "/sig_W5") (class "Default") (node (ref "J1") (pin "W5") (pintype "input")))
    (net (code "220") (name "/sig_W6") (class "Default") (node (ref "J1") (pin "W6") (pintype "input")))
    (net (code "221") (name "/sig_W7") (class "Default") (node (ref "J1") (pin "W7") (pintype "input")))
    (net (code "222") (name "/sig_W8") (class "Default") (node (ref "J1") (pin "W8") (pintype "input")))
    (net (code "223") (name "/sig_W9") (class "Default") (node (ref "J1") (pin "W9") (pintype "input")))
    (net (code "224") (name "/sig_W10") (class "Default") (node (ref "J1") (pin "W10") (pintype "input")))
    (net (code "225") (name "/sig_W11") (class "Default") (node (ref "J1") (pin "W11") (pintype "input")))
    (net (code "226") (name "/sig_W12") (class "Default") (node (ref "J1") (pin "W12") (pintype "input")))
    (net (code "227") (name "/sig_W13") (class "Default") (node (ref "J1") (pin "W13") (pintype "input")))
    (net (code "228") (name "/sig_W14") (class "Default") (node (ref "J1") (pin "W14") (pintype "input")))
    (net (code "229") (name "/sig_W15") (class "Default") (node (ref "J1") (pin "W15") (pintype "input")))
    (net (code "230") (name "/sig_W16") (class "Default") (node (ref "J1") (pin "W16") (pintype "input")))
    (net (code "231") (name "/sig_W17") (class "Default") (node (ref "J1") (pin "W17") (pintype "input")))
    (net (code "232") (name "/sig_W18") (class "Default") (node (ref "J1") (pin "W18") (pintype "input")))
    (net (code "233") (name "/sig_W19") (class "Default") (node (ref "J1") (pin "W19") (pintype "input")))
    (net (code "234") (name "/us__CML_clk_n") (class "Default")
      (node (ref "J1") (pin "D6") (pintype "input"))
    )
    (net (code "235") (name "/us__CML_clk_p") (class "Default")
      (node (ref "J1") (pin "D5") (pintype "input"))
    )
    (net (code "236") (name "/us__rx_out_0_n") (class "Default")
      (node (ref "J1") (pin "D4") (pintype "input"))
    )
    (net (code "237") (name "/us__rx_out_0_p") (class "Default")
      (node (ref "J1") (pin "E4") (pintype "input"))
    )
    (net (code "238") (name "/us__rx_out_1_n") (class "Default")
      (node (ref "J1") (pin "E12") (pintype "input"))
    )
    (net (code "239") (name "/us__rx_out_1_p") (class "Default")
      (node (ref "J1") (pin "E11") (pintype "input"))
    )
    (net (code "240") (name "/us__rx_out_2_n") (class "Default")
      (node (ref "J1") (pin "D12") (pintype "input"))
    )
    (net (code "241") (name "/us__rx_out_2_p") (class "Default")
      (node (ref "J1") (pin "D11") (pintype "input"))
    )
    (net (code "242") (name "/us__rx_out_3_n") (class "Default")
      (node (ref "J1") (pin "M5") (pintype "input"))
    )
    (net (code "243") (name "/us__rx_out_3_p") (class "Default")
      (node (ref "J1") (pin "M4") (pintype "input"))
    )
    (net (code "244") (name "/us__rx_out_4_n") (class "Default")
      (node (ref "J1") (pin "K4") (pintype "input"))
    )
    (net (code "245") (name "/us__rx_out_4_p") (class "Default")
      (node (ref "J1") (pin "L4") (pintype "input"))
    )
    (net (code "246") (name "/us__rx_out_5_n") (class "Default")
      (node (ref "J1") (pin "D10") (pintype "input"))
    )
    (net (code "247") (name "/us__rx_out_5_p") (class "Default")
      (node (ref "J1") (pin "D9") (pintype "input"))
    )
    (net (code "248") (name "/us__rx_out_6_n") (class "Default")
      (node (ref "J1") (pin "D8") (pintype "input"))
    )
    (net (code "249") (name "/us__rx_out_6_p") (class "Default")
      (node (ref "J1") (pin "D7") (pintype "input"))
    )
    (net (code "250") (name "/us__rx_out_7_n") (class "Default")
      (node (ref "J1") (pin "K5") (pintype "input"))
    )
    (net (code "251") (name "/us__rx_out_7_p") (class "Default")
      (node (ref "J1") (pin "L5") (pintype "input"))
    )
    (net (code "252") (name "/us__rx_out_8_n") (class "Default")
      (node (ref "J1") (pin "J5") (pintype "input"))
    )
    (net (code "253") (name "/us__rx_out_8_p") (class "Default")
      (node (ref "J1") (pin "H5") (pintype "input"))
    )
    (net (code "254") (name "/us__rx_out_9_n") (class "Default")
      (node (ref "J1") (pin "E8") (pintype "input"))
    )
    (net (code "255") (name "/us__rx_out_9_p") (class "Default")
      (node (ref "J1") (pin "E7") (pintype "input"))
    )
    (net (code "256") (name "/us__rx_out_10_n") (class "Default")
      (node (ref "J1") (pin "E9") (pintype "input"))
    )
    (net (code "257") (name "/us__rx_out_10_p") (class "Default")
      (node (ref "J1") (pin "E10") (pintype "input"))
    )
    (net (code "258") (name "/us__rx_out_11_n") (class "Default")
      (node (ref "J1") (pin "G5") (pintype "input"))
    )
    (net (code "259") (name "/us__rx_out_11_p") (class "Default")
      (node (ref "J1") (pin "F5") (pintype "input"))
    )
    (net (code "260") (name "/us__rx_out_12_n") (class "Default")
      (node (ref "J1") (pin "G4") (pintype "input"))
    )
    (net (code "261") (name "/us__rx_out_12_p") (class "Default")
      (node (ref "J1") (pin "F4") (pintype "input"))
    )
    (net (code "262") (name "/us__rx_out_13_n") (class "Default")
      (node (ref "J1") (pin "E5") (pintype "input"))
    )
    (net (code "263") (name "/us__rx_out_13_p") (class "Default")
      (node (ref "J1") (pin "E6") (pintype "input"))
    )
    (net (code "264") (name "/us__rx_out_14_n") (class "Default")
      (node (ref "J1") (pin "J4") (pintype "input"))
    )
    (net (code "265") (name "/us__rx_out_14_p") (class "Default")
      (node (ref "J1") (pin "H4") (pintype "input"))
    )
    (net (code "266") (name "unconnected-(J2-Pad1)") (class "Default")
      (node (ref "J2") (pin "1") (pinfunction "1_1") (pintype "passive"))
    )
    (net (code "267") (name "unconnected-(J2-Pad2)") (class "Default")
      (node (ref "J2") (pin "2") (pinfunction "2_2") (pintype "passive"))
    )
    (net (code "268") (name "unconnected-(J2-Pad3)") (class "Default")
      (node (ref "J2") (pin "3") (pinfunction "3_3") (pintype "passive"))
    )
    (net (code "269") (name "unconnected-(J2-Pad4)") (class "Default")
      (node (ref "J2") (pin "4") (pinfunction "4_4") (pintype "passive"))
    )
    (net (code "270") (name "unconnected-(J2-Pad5)") (class "Default")
      (node (ref "J2") (pin "5") (pinfunction "5_5") (pintype "passive"))
    )
    (net (code "271") (name "unconnected-(J2-Pad6)") (class "Default")
      (node (ref "J2") (pin "6") (pinfunction "6_6") (pintype "passive"))
    )
    (net (code "272") (name "unconnected-(J2-Pad7)") (class "Default")
      (node (ref "J2") (pin "7") (pinfunction "7_7") (pintype "passive"))
    )
    (net (code "273") (name "unconnected-(J2-Pad8)") (class "Default")
      (node (ref "J2") (pin "8") (pinfunction "8_8") (pintype "passive"))
    )
    (net (code "274") (name "unconnected-(J2-Pad9)") (class "Default")
      (node (ref "J2") (pin "9") (pinfunction "9_9") (pintype "passive"))
    )
    (net (code "275") (name "unconnected-(J2-Pad10)") (class "Default")
      (node (ref "J2") (pin "10") (pinfunction "10_10") (pintype "passive"))
    )
    (net (code "276") (name "unconnected-(J2-Pad11)") (class "Default")
      (node (ref "J2") (pin "11") (pinfunction "11_11") (pintype "passive"))
    )
    (net (code "277") (name "unconnected-(J2-Pad12)") (class "Default")
      (node (ref "J2") (pin "12") (pinfunction "12_12") (pintype "passive"))
    )
    (net (code "278") (name "unconnected-(J2-Pad13)") (class "Default")
      (node (ref "J2") (pin "13") (pinfunction "13_13") (pintype "passive"))
    )
    (net (code "279") (name "unconnected-(J2-Pad14)") (class "Default")
      (node (ref "J2") (pin "14") (pinfunction "14_14") (pintype "passive"))
    )
    (net (code "280") (name "unconnected-(J2-Pad15)") (class "Default")
      (node (ref "J2") (pin "15") (pinfunction "15_15") (pintype "passive"))
    )
    (net (code "281") (name "unconnected-(J2-Pad16)") (class "Default")
      (node (ref "J2") (pin "16") (pinfunction "16_16") (pintype "passive"))
    )
    (net (code "282") (name "unconnected-(J2-Pad17)") (class "Default")
      (node (ref "J2") (pin "17") (pinfunction "17_17") (pintype "passive"))
    )
    (net (code "283") (name "unconnected-(J2-Pad18)") (class "Default")
      (node (ref "J2") (pin "18") (pinfunction "18_18") (pintype "passive"))
    )
    (net (code "284") (name "unconnected-(J2-Pad19)") (class "Default")
      (node (ref "J2") (pin "19") (pinfunction "19_19") (pintype "passive"))
    )
    (net (code "285") (name "unconnected-(J2-Pad20)") (class "Default")
      (node (ref "J2") (pin "20") (pinfunction "20_20") (pintype "passive"))
    )
    (net (code "286") (name "unconnected-(J2-Pad21)") (class "Default")
      (node (ref "J2") (pin "21") (pinfunction "21_21") (pintype "passive"))
    )
    (net (code "287") (name "unconnected-(J2-Pad22)") (class "Default")
      (node (ref "J2") (pin "22") (pinfunction "22_22") (pintype "passive"))
    )
    (net (code "288") (name "unconnected-(J2-Pad23)") (class "Default")
      (node (ref "J2") (pin "23") (pinfunction "23_23") (pintype "passive"))
    )
    (net (code "289") (name "unconnected-(J2-Pad24)") (class "Default")
      (node (ref "J2") (pin "24") (pinfunction "24_24") (pintype "passive"))
    )
    (net (code "290") (name "unconnected-(J2-Pad25)") (class "Default")
      (node (ref "J2") (pin "25") (pinfunction "25_25") (pintype "passive"))
    )
    (net (code "291") (name "unconnected-(J2-Pad26)") (class "Default")
      (node (ref "J2") (pin "26") (pinfunction "26_26") (pintype "passive"))
    )
    (net (code "292") (name "unconnected-(J2-Pad27)") (class "Default")
      (node (ref "J2") (pin "27") (pinfunction "27_27") (pintype "passive"))
    )
    (net (code "293") (name "unconnected-(J2-Pad28)") (class "Default")
      (node (ref "J2") (pin "28") (pinfunction "28_28") (pintype "passive"))
    )
    (net (code "294") (name "unconnected-(J2-Pad29)") (class "Default")
      (node (ref "J2") (pin "29") (pinfunction "29_29") (pintype "passive"))
    )
    (net (code "295") (name "unconnected-(J2-Pad30)") (class "Default")
      (node (ref "J2") (pin "30") (pinfunction "30_30") (pintype "passive"))
    )
    (net (code "296") (name "unconnected-(J2-Pad31)") (class "Default")
      (node (ref "J2") (pin "31") (pinfunction "31_31") (pintype "passive"))
    )
    (net (code "297") (name "unconnected-(J2-Pad32)") (class "Default")
      (node (ref "J2") (pin "32") (pinfunction "32_32") (pintype "passive"))
    )
    (net (code "298") (name "unconnected-(J2-Pad33)") (class "Default")
      (node (ref "J2") (pin "33") (pinfunction "33_33") (pintype "passive"))
    )
    (net (code "299") (name "unconnected-(J2-Pad34)") (class "Default")
      (node (ref "J2") (pin "34") (pinfunction "34_34") (pintype "passive"))
    )
    (net (code "300") (name "unconnected-(J2-Pad35)") (class "Default")
      (node (ref "J2") (pin "35") (pinfunction "35_35") (pintype "passive"))
    )
    (net (code "301") (name "unconnected-(J2-Pad36)") (class "Default")
      (node (ref "J2") (pin "36") (pinfunction "36_36") (pintype "passive"))
    )
    (net (code "302") (name "unconnected-(J2-Pad37)") (class "Default")
      (node (ref "J2") (pin "37") (pinfunction "37_37") (pintype "passive"))
    )
    (net (code "303") (name "unconnected-(J2-Pad38)") (class "Default")
      (node (ref "J2") (pin "38") (pinfunction "38_38") (pintype "passive"))
    )
    (net (code "304") (name "unconnected-(J2-Pad39)") (class "Default")
      (node (ref "J2") (pin "39") (pinfunction "39_39") (pintype "passive"))
    )
    (net (code "305") (name "unconnected-(J2-Pad40)") (class "Default")
      (node (ref "J2") (pin "40") (pinfunction "40_40") (pintype "passive"))
    )
    (net (code "306") (name "unconnected-(J2-Pad41)") (class "Default")
      (node (ref "J2") (pin "41") (pinfunction "41_41") (pintype "passive"))
    )
    (net (code "307") (name "unconnected-(J2-Pad42)") (class "Default")
      (node (ref "J2") (pin "42") (pinfunction "42_42") (pintype "passive"))
    )
    (net (code "308") (name "unconnected-(J2-Pad43)") (class "Default")
      (node (ref "J2") (pin "43") (pinfunction "43_43") (pintype "passive"))
    )
    (net (code "309") (name "unconnected-(J2-Pad44)") (class "Default")
      (node (ref "J2") (pin "44") (pinfunction "44_44") (pintype "passive"))
    )
    (net (code "310") (name "unconnected-(J2-Pad45)") (class "Default")
      (node (ref "J2") (pin "45") (pinfunction "45_45") (pintype "passive"))
    )
    (net (code "311") (name "unconnected-(J2-Pad46)") (class "Default")
      (node (ref "J2") (pin "46") (pinfunction "46_46") (pintype "passive"))
    )
    (net (code "312") (name "unconnected-(J2-Pad47)") (class "Default")
      (node (ref "J2") (pin "47") (pinfunction "47_47") (pintype "passive"))
    )
    (net (code "313") (name "unconnected-(J2-Pad48)") (class "Default")
      (node (ref "J2") (pin "48") (pinfunction "48_48") (pintype "passive"))
    )
    (net (code "314") (name "unconnected-(J2-Pad49)") (class "Default")
      (node (ref "J2") (pin "49") (pinfunction "49_49") (pintype "passive"))
    )
    (net (code "315") (name "unconnected-(J2-Pad50)") (class "Default")
      (node (ref "J2") (pin "50") (pinfunction "50_50") (pintype "passive"))
    )
    (net (code "316") (name "unconnected-(J3-Pad1)") (class "Default")
      (node (ref "J3") (pin "1") (pinfunction "1_1") (pintype "passive"))
    )
    (net (code "317") (name "unconnected-(J3-Pad2)") (class "Default")
      (node (ref "J3") (pin "2") (pinfunction "2_2") (pintype "passive"))
    )
    (net (code "318") (name "unconnected-(J3-Pad3)") (class "Default")
      (node (ref "J3") (pin "3") (pinfunction "3_3") (pintype "passive"))
    )
    (net (code "319") (name "unconnected-(J3-Pad4)") (class "Default")
      (node (ref "J3") (pin "4") (pinfunction "4_4") (pintype "passive"))
    )
    (net (code "320") (name "unconnected-(J3-Pad5)") (class "Default")
      (node (ref "J3") (pin "5") (pinfunction "5_5") (pintype "passive"))
    )
    (net (code "321") (name "unconnected-(J3-Pad6)") (class "Default")
      (node (ref "J3") (pin "6") (pinfunction "6_6") (pintype "passive"))
    )
    (net (code "322") (name "unconnected-(J3-Pad7)") (class "Default")
      (node (ref "J3") (pin "7") (pinfunction "7_7") (pintype "passive"))
    )
    (net (code "323") (name "unconnected-(J3-Pad8)") (class "Default")
      (node (ref "J3") (pin "8") (pinfunction "8_8") (pintype "passive"))
    )
    (net (code "324") (name "unconnected-(J3-Pad9)") (class "Default")
      (node (ref "J3") (pin "9") (pinfunction "9_9") (pintype "passive"))
    )
    (net (code "325") (name "unconnected-(J3-Pad10)") (class "Default")
      (node (ref "J3") (pin "10") (pinfunction "10_10") (pintype "passive"))
    )
    (net (code "326") (name "unconnected-(J3-Pad11)") (class "Default")
      (node (ref "J3") (pin "11") (pinfunction "11_11") (pintype "passive"))
    )
    (net (code "327") (name "unconnected-(J3-Pad12)") (class "Default")
      (node (ref "J3") (pin "12") (pinfunction "12_12") (pintype "passive"))
    )
    (net (code "328") (name "unconnected-(J3-Pad13)") (class "Default")
      (node (ref "J3") (pin "13") (pinfunction "13_13") (pintype "passive"))
    )
    (net (code "329") (name "unconnected-(J3-Pad14)") (class "Default")
      (node (ref "J3") (pin "14") (pinfunction "14_14") (pintype "passive"))
    )
    (net (code "330") (name "unconnected-(J3-Pad15)") (class "Default")
      (node (ref "J3") (pin "15") (pinfunction "15_15") (pintype "passive"))
    )
    (net (code "331") (name "unconnected-(J3-Pad16)") (class "Default")
      (node (ref "J3") (pin "16") (pinfunction "16_16") (pintype "passive"))
    )
    (net (code "332") (name "unconnected-(J3-Pad17)") (class "Default")
      (node (ref "J3") (pin "17") (pinfunction "17_17") (pintype "passive"))
    )
    (net (code "333") (name "unconnected-(J3-Pad18)") (class "Default")
      (node (ref "J3") (pin "18") (pinfunction "18_18") (pintype "passive"))
    )
    (net (code "334") (name "unconnected-(J3-Pad19)") (class "Default")
      (node (ref "J3") (pin "19") (pinfunction "19_19") (pintype "passive"))
    )
    (net (code "335") (name "unconnected-(J3-Pad20)") (class "Default")
      (node (ref "J3") (pin "20") (pinfunction "20_20") (pintype "passive"))
    )
    (net (code "336") (name "unconnected-(J3-Pad21)") (class "Default")
      (node (ref "J3") (pin "21") (pinfunction "21_21") (pintype "passive"))
    )
    (net (code "337") (name "unconnected-(J3-Pad22)") (class "Default")
      (node (ref "J3") (pin "22") (pinfunction "22_22") (pintype "passive"))
    )
    (net (code "338") (name "unconnected-(J3-Pad23)") (class "Default")
      (node (ref "J3") (pin "23") (pinfunction "23_23") (pintype "passive"))
    )
    (net (code "339") (name "unconnected-(J3-Pad24)") (class "Default")
      (node (ref "J3") (pin "24") (pinfunction "24_24") (pintype "passive"))
    )
    (net (code "340") (name "unconnected-(J3-Pad25)") (class "Default")
      (node (ref "J3") (pin "25") (pinfunction "25_25") (pintype "passive"))
    )
    (net (code "341") (name "unconnected-(J3-Pad26)") (class "Default")
      (node (ref "J3") (pin "26") (pinfunction "26_26") (pintype "passive"))
    )
    (net (code "342") (name "unconnected-(J3-Pad27)") (class "Default")
      (node (ref "J3") (pin "27") (pinfunction "27_27") (pintype "passive"))
    )
    (net (code "343") (name "unconnected-(J3-Pad28)") (class "Default")
      (node (ref "J3") (pin "28") (pinfunction "28_28") (pintype "passive"))
    )
    (net (code "344") (name "unconnected-(J3-Pad29)") (class "Default")
      (node (ref "J3") (pin "29") (pinfunction "29_29") (pintype "passive"))
    )
    (net (code "345") (name "unconnected-(J3-Pad30)") (class "Default")
      (node (ref "J3") (pin "30") (pinfunction "30_30") (pintype "passive"))
    )
    (net (code "346") (name "unconnected-(J3-Pad31)") (class "Default")
      (node (ref "J3") (pin "31") (pinfunction "31_31") (pintype "passive"))
    )
    (net (code "347") (name "unconnected-(J3-Pad32)") (class "Default")
      (node (ref "J3") (pin "32") (pinfunction "32_32") (pintype "passive"))
    )
    (net (code "348") (name "unconnected-(J3-Pad33)") (class "Default")
      (node (ref "J3") (pin "33") (pinfunction "33_33") (pintype "passive"))
    )
    (net (code "349") (name "unconnected-(J3-Pad34)") (class "Default")
      (node (ref "J3") (pin "34") (pinfunction "34_34") (pintype "passive"))
    )
    (net (code "350") (name "unconnected-(J3-Pad35)") (class "Default")
      (node (ref "J3") (pin "35") (pinfunction "35_35") (pintype "passive"))
    )
    (net (code "351") (name "unconnected-(J3-Pad36)") (class "Default")
      (node (ref "J3") (pin "36") (pinfunction "36_36") (pintype "passive"))
    )
    (net (code "352") (name "unconnected-(J3-Pad37)") (class "Default")
      (node (ref "J3") (pin "37") (pinfunction "37_37") (pintype "passive"))
    )
    (net (code "353") (name "unconnected-(J3-Pad38)") (class "Default")
      (node (ref "J3") (pin "38") (pinfunction "38_38") (pintype "passive"))
    )
    (net (code "354") (name "unconnected-(J3-Pad39)") (class "Default")
      (node (ref "J3") (pin "39") (pinfunction "39_39") (pintype "passive"))
    )
    (net (code "355") (name "unconnected-(J3-Pad40)") (class "Default")
      (node (ref "J3") (pin "40") (pinfunction "40_40") (pintype "passive"))
    )
    (net (code "356") (name "unconnected-(J3-Pad41)") (class "Default")
      (node (ref "J3") (pin "41") (pinfunction "41_41") (pintype "passive"))
    )
    (net (code "357") (name "unconnected-(J3-Pad42)") (class "Default")
      (node (ref "J3") (pin "42") (pinfunction "42_42") (pintype "passive"))
    )
    (net (code "358") (name "unconnected-(J3-Pad43)") (class "Default")
      (node (ref "J3") (pin "43") (pinfunction "43_43") (pintype "passive"))
    )
    (net (code "359") (name "unconnected-(J3-Pad44)") (class "Default")
      (node (ref "J3") (pin "44") (pinfunction "44_44") (pintype "passive"))
    )
    (net (code "360") (name "unconnected-(J3-Pad45)") (class "Default")
      (node (ref "J3") (pin "45") (pinfunction "45_45") (pintype "passive"))
    )
    (net (code "361") (name "unconnected-(J3-Pad46)") (class "Default")
      (node (ref "J3") (pin "46") (pinfunction "46_46") (pintype "passive"))
    )
    (net (code "362") (name "unconnected-(J3-Pad47)") (class "Default")
      (node (ref "J3") (pin "47") (pinfunction "47_47") (pintype "passive"))
    )
    (net (code "363") (name "unconnected-(J3-Pad48)") (class "Default")
      (node (ref "J3") (pin "48") (pinfunction "48_48") (pintype "passive"))
    )
    (net (code "364") (name "unconnected-(J3-Pad49)") (class "Default")
      (node (ref "J3") (pin "49") (pinfunction "49_49") (pintype "passive"))
    )
    (net (code "365") (name "unconnected-(J3-Pad50)") (class "Default")
      (node (ref "J3") (pin "50") (pinfunction "50_50") (pintype "passive"))
    )
  )
)
